# left.net
KiCad netlist of a schematic drawn in EAGLE
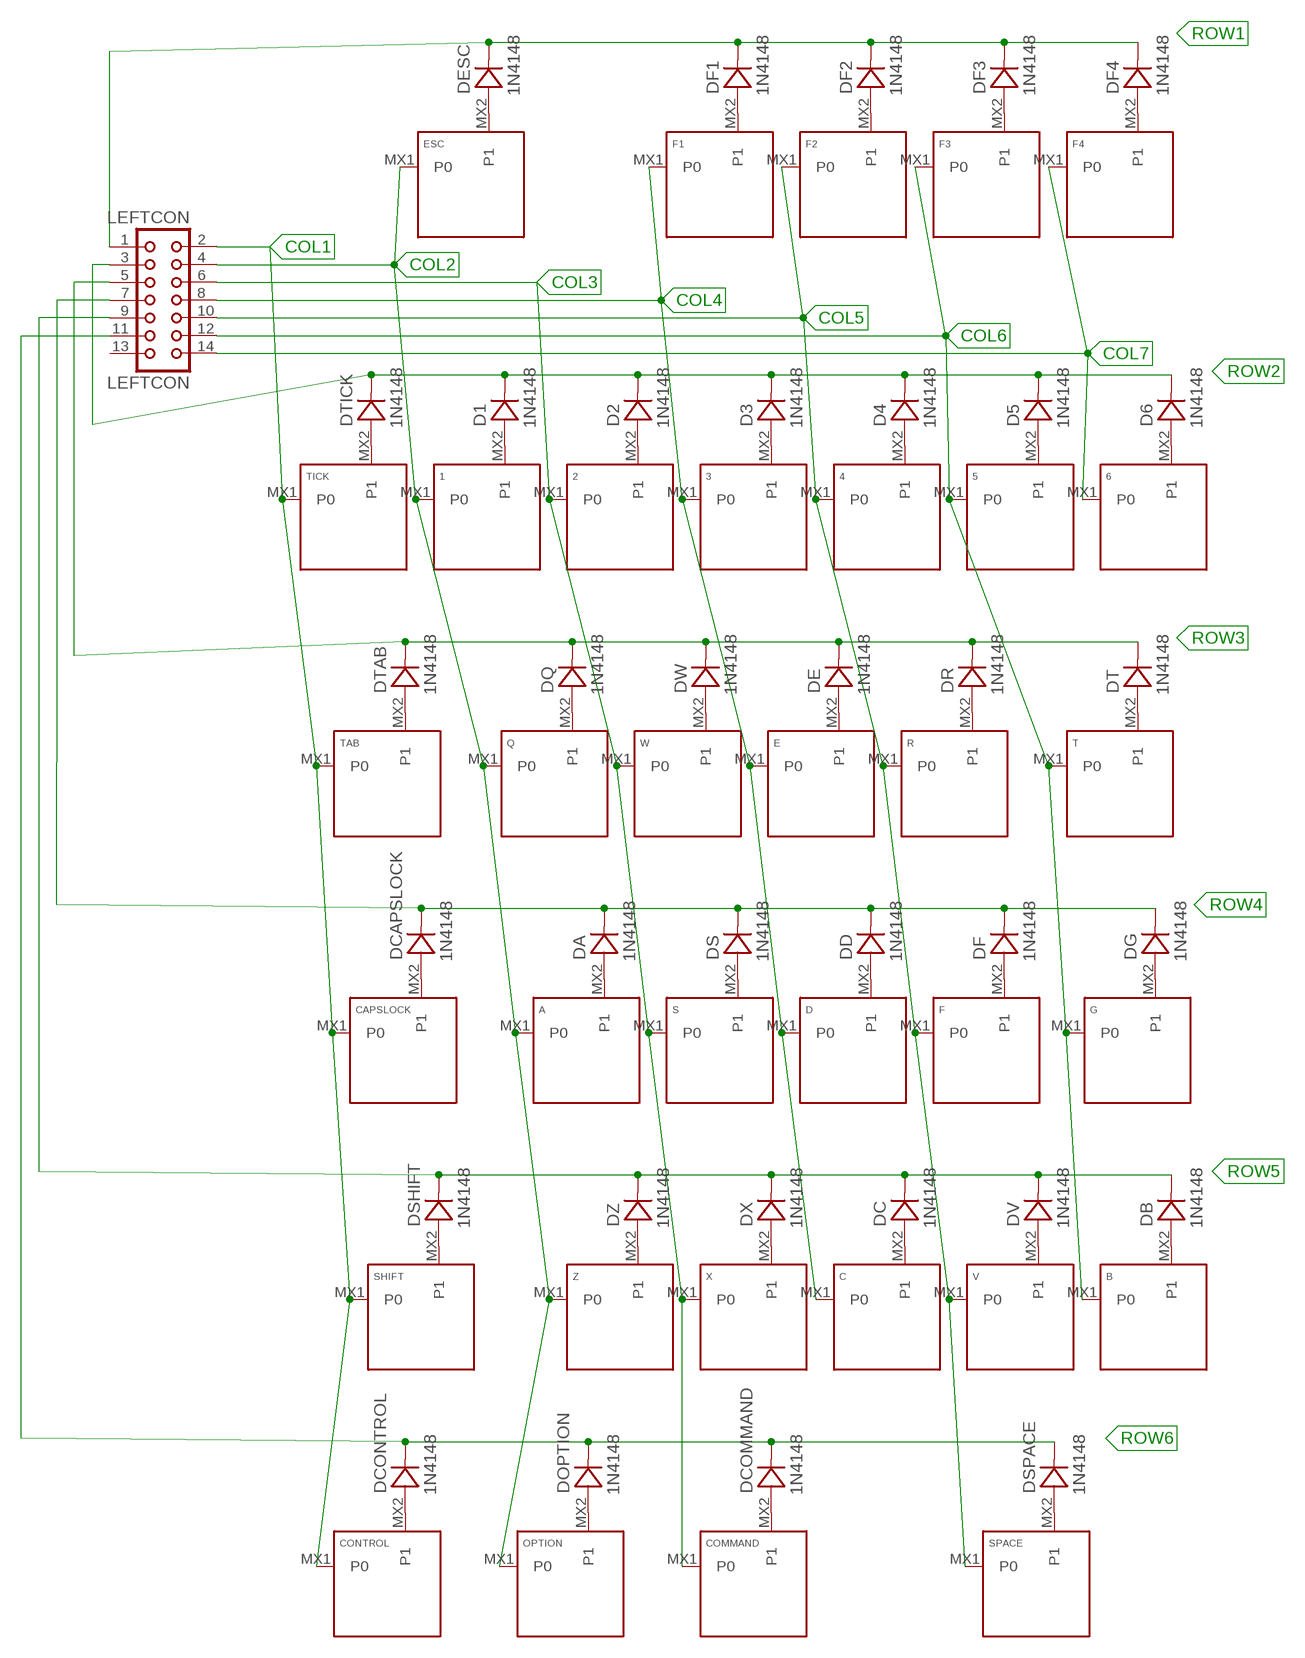
[diagram p0: schematic, sheet 1]

(export (version "E")
  (design (tool "Eeschema 10.0.6"))
  (components
    (comp (ref "1")
      (value "KEYSWITCH-PLAIN-MX-1U")
      (footprint "eagle-import:MX-1U")
      (libsource (lib "eagle-import") (part "KEYSWITCH-PLAIN-MX-1U"))
    )
    (comp (ref "2")
      (value "KEYSWITCH-PLAIN-MX-1U")
      (footprint "eagle-import:MX-1U")
      (libsource (lib "eagle-import") (part "KEYSWITCH-PLAIN-MX-1U"))
    )
    (comp (ref "3")
      (value "KEYSWITCH-PLAIN-MX-1U")
      (footprint "eagle-import:MX-1U")
      (libsource (lib "eagle-import") (part "KEYSWITCH-PLAIN-MX-1U"))
    )
    (comp (ref "4")
      (value "KEYSWITCH-PLAIN-MX-1U")
      (footprint "eagle-import:MX-1U")
      (libsource (lib "eagle-import") (part "KEYSWITCH-PLAIN-MX-1U"))
    )
    (comp (ref "5")
      (value "KEYSWITCH-PLAIN-MX-1U")
      (footprint "eagle-import:MX-1U")
      (libsource (lib "eagle-import") (part "KEYSWITCH-PLAIN-MX-1U"))
    )
    (comp (ref "6")
      (value "KEYSWITCH-PLAIN-MX-1U")
      (footprint "eagle-import:MX-1U")
      (libsource (lib "eagle-import") (part "KEYSWITCH-PLAIN-MX-1U"))
    )
    (comp (ref "A")
      (value "KEYSWITCH-PLAIN-MX-1U")
      (footprint "eagle-import:MX-1U")
      (libsource (lib "eagle-import") (part "KEYSWITCH-PLAIN-MX-1U"))
    )
    (comp (ref "B")
      (value "KEYSWITCH-PLAIN-MX-1U")
      (footprint "eagle-import:MX-1U")
      (libsource (lib "eagle-import") (part "KEYSWITCH-PLAIN-MX-1U"))
    )
    (comp (ref "C")
      (value "KEYSWITCH-PLAIN-MX-1U")
      (footprint "eagle-import:MX-1U")
      (libsource (lib "eagle-import") (part "KEYSWITCH-PLAIN-MX-1U"))
    )
    (comp (ref "CAPSLOCK")
      (value "KEYSWITCH-PLAIN-MX-1U")
      (footprint "eagle-import:MX-1U")
      (libsource (lib "eagle-import") (part "KEYSWITCH-PLAIN-MX-1U"))
    )
    (comp (ref "COMMAND")
      (value "KEYSWITCH-PLAIN-MX-1U")
      (footprint "eagle-import:MX-1U")
      (libsource (lib "eagle-import") (part "KEYSWITCH-PLAIN-MX-1U"))
    )
    (comp (ref "CONTROL")
      (value "KEYSWITCH-PLAIN-MX-1U")
      (footprint "eagle-import:MX-1U")
      (libsource (lib "eagle-import") (part "KEYSWITCH-PLAIN-MX-1U"))
    )
    (comp (ref "D")
      (value "KEYSWITCH-PLAIN-MX-1U")
      (footprint "eagle-import:MX-1U")
      (libsource (lib "eagle-import") (part "KEYSWITCH-PLAIN-MX-1U"))
    )
    (comp (ref "D1")
      (value "1N4148")
      (footprint "eagle-import:DO-35")
      (libsource (lib "eagle-import") (part "DIODE-DO-35"))
    )
    (comp (ref "D2")
      (value "1N4148")
      (footprint "eagle-import:DO-35")
      (libsource (lib "eagle-import") (part "DIODE-DO-35"))
    )
    (comp (ref "D3")
      (value "1N4148")
      (footprint "eagle-import:DO-35")
      (libsource (lib "eagle-import") (part "DIODE-DO-35"))
    )
    (comp (ref "D4")
      (value "1N4148")
      (footprint "eagle-import:DO-35")
      (libsource (lib "eagle-import") (part "DIODE-DO-35"))
    )
    (comp (ref "D5")
      (value "1N4148")
      (footprint "eagle-import:DO-35")
      (libsource (lib "eagle-import") (part "DIODE-DO-35"))
    )
    (comp (ref "D6")
      (value "1N4148")
      (footprint "eagle-import:DO-35")
      (libsource (lib "eagle-import") (part "DIODE-DO-35"))
    )
    (comp (ref "DA")
      (value "1N4148")
      (footprint "eagle-import:DO-35")
      (libsource (lib "eagle-import") (part "DIODE-DO-35"))
    )
    (comp (ref "DB")
      (value "1N4148")
      (footprint "eagle-import:DO-35")
      (libsource (lib "eagle-import") (part "DIODE-DO-35"))
    )
    (comp (ref "DC")
      (value "1N4148")
      (footprint "eagle-import:DO-35")
      (libsource (lib "eagle-import") (part "DIODE-DO-35"))
    )
    (comp (ref "DCAPSLOCK")
      (value "1N4148")
      (footprint "eagle-import:DO-35")
      (libsource (lib "eagle-import") (part "DIODE-DO-35"))
    )
    (comp (ref "DCOMMAND")
      (value "1N4148")
      (footprint "eagle-import:DO-35")
      (libsource (lib "eagle-import") (part "DIODE-DO-35"))
    )
    (comp (ref "DCONTROL")
      (value "1N4148")
      (footprint "eagle-import:DO-35")
      (libsource (lib "eagle-import") (part "DIODE-DO-35"))
    )
    (comp (ref "DD")
      (value "1N4148")
      (footprint "eagle-import:DO-35")
      (libsource (lib "eagle-import") (part "DIODE-DO-35"))
    )
    (comp (ref "DE")
      (value "1N4148")
      (footprint "eagle-import:DO-35")
      (libsource (lib "eagle-import") (part "DIODE-DO-35"))
    )
    (comp (ref "DESC")
      (value "1N4148")
      (footprint "eagle-import:DO-35")
      (libsource (lib "eagle-import") (part "DIODE-DO-35"))
    )
    (comp (ref "DF")
      (value "1N4148")
      (footprint "eagle-import:DO-35")
      (libsource (lib "eagle-import") (part "DIODE-DO-35"))
    )
    (comp (ref "DF1")
      (value "1N4148")
      (footprint "eagle-import:DO-35")
      (libsource (lib "eagle-import") (part "DIODE-DO-35"))
    )
    (comp (ref "DF2")
      (value "1N4148")
      (footprint "eagle-import:DO-35")
      (libsource (lib "eagle-import") (part "DIODE-DO-35"))
    )
    (comp (ref "DF3")
      (value "1N4148")
      (footprint "eagle-import:DO-35")
      (libsource (lib "eagle-import") (part "DIODE-DO-35"))
    )
    (comp (ref "DF4")
      (value "1N4148")
      (footprint "eagle-import:DO-35")
      (libsource (lib "eagle-import") (part "DIODE-DO-35"))
    )
    (comp (ref "DG")
      (value "1N4148")
      (footprint "eagle-import:DO-35")
      (libsource (lib "eagle-import") (part "DIODE-DO-35"))
    )
    (comp (ref "DOPTION")
      (value "1N4148")
      (footprint "eagle-import:DO-35")
      (libsource (lib "eagle-import") (part "DIODE-DO-35"))
    )
    (comp (ref "DQ")
      (value "1N4148")
      (footprint "eagle-import:DO-35")
      (libsource (lib "eagle-import") (part "DIODE-DO-35"))
    )
    (comp (ref "DR")
      (value "1N4148")
      (footprint "eagle-import:DO-35")
      (libsource (lib "eagle-import") (part "DIODE-DO-35"))
    )
    (comp (ref "DS")
      (value "1N4148")
      (footprint "eagle-import:DO-35")
      (libsource (lib "eagle-import") (part "DIODE-DO-35"))
    )
    (comp (ref "DSHIFT")
      (value "1N4148")
      (footprint "eagle-import:DO-35")
      (libsource (lib "eagle-import") (part "DIODE-DO-35"))
    )
    (comp (ref "DSPACE")
      (value "1N4148")
      (footprint "eagle-import:DO-35")
      (libsource (lib "eagle-import") (part "DIODE-DO-35"))
    )
    (comp (ref "DT")
      (value "1N4148")
      (footprint "eagle-import:DO-35")
      (libsource (lib "eagle-import") (part "DIODE-DO-35"))
    )
    (comp (ref "DTAB")
      (value "1N4148")
      (footprint "eagle-import:DO-35")
      (libsource (lib "eagle-import") (part "DIODE-DO-35"))
    )
    (comp (ref "DTICK")
      (value "1N4148")
      (footprint "eagle-import:DO-35")
      (libsource (lib "eagle-import") (part "DIODE-DO-35"))
    )
    (comp (ref "DV")
      (value "1N4148")
      (footprint "eagle-import:DO-35")
      (libsource (lib "eagle-import") (part "DIODE-DO-35"))
    )
    (comp (ref "DW")
      (value "1N4148")
      (footprint "eagle-import:DO-35")
      (libsource (lib "eagle-import") (part "DIODE-DO-35"))
    )
    (comp (ref "DX")
      (value "1N4148")
      (footprint "eagle-import:DO-35")
      (libsource (lib "eagle-import") (part "DIODE-DO-35"))
    )
    (comp (ref "DZ")
      (value "1N4148")
      (footprint "eagle-import:DO-35")
      (libsource (lib "eagle-import") (part "DIODE-DO-35"))
    )
    (comp (ref "E")
      (value "KEYSWITCH-PLAIN-MX-1U")
      (footprint "eagle-import:MX-1U")
      (libsource (lib "eagle-import") (part "KEYSWITCH-PLAIN-MX-1U"))
    )
    (comp (ref "ESC")
      (value "KEYSWITCH-PLAIN-MX-1U")
      (footprint "eagle-import:MX-1U")
      (libsource (lib "eagle-import") (part "KEYSWITCH-PLAIN-MX-1U"))
    )
    (comp (ref "F")
      (value "KEYSWITCH-PLAIN-MX-1U")
      (footprint "eagle-import:MX-1U")
      (libsource (lib "eagle-import") (part "KEYSWITCH-PLAIN-MX-1U"))
    )
    (comp (ref "F1")
      (value "KEYSWITCH-PLAIN-MX-1U")
      (footprint "eagle-import:MX-1U")
      (libsource (lib "eagle-import") (part "KEYSWITCH-PLAIN-MX-1U"))
    )
    (comp (ref "F2")
      (value "KEYSWITCH-PLAIN-MX-1U")
      (footprint "eagle-import:MX-1U")
      (libsource (lib "eagle-import") (part "KEYSWITCH-PLAIN-MX-1U"))
    )
    (comp (ref "F3")
      (value "KEYSWITCH-PLAIN-MX-1U")
      (footprint "eagle-import:MX-1U")
      (libsource (lib "eagle-import") (part "KEYSWITCH-PLAIN-MX-1U"))
    )
    (comp (ref "F4")
      (value "KEYSWITCH-PLAIN-MX-1U")
      (footprint "eagle-import:MX-1U")
      (libsource (lib "eagle-import") (part "KEYSWITCH-PLAIN-MX-1U"))
    )
    (comp (ref "G")
      (value "KEYSWITCH-PLAIN-MX-1U")
      (footprint "eagle-import:MX-1U")
      (libsource (lib "eagle-import") (part "KEYSWITCH-PLAIN-MX-1U"))
    )
    (comp (ref "LEFTCON")
      (value "LEFTCON")
      (footprint "eagle-import:CON14")
      (libsource (lib "eagle-import") (part "CON14"))
    )
    (comp (ref "OPTION")
      (value "KEYSWITCH-PLAIN-MX-1U")
      (footprint "eagle-import:MX-1U")
      (libsource (lib "eagle-import") (part "KEYSWITCH-PLAIN-MX-1U"))
    )
    (comp (ref "Q")
      (value "KEYSWITCH-PLAIN-MX-1U")
      (footprint "eagle-import:MX-1U")
      (libsource (lib "eagle-import") (part "KEYSWITCH-PLAIN-MX-1U"))
    )
    (comp (ref "R")
      (value "KEYSWITCH-PLAIN-MX-1U")
      (footprint "eagle-import:MX-1U")
      (libsource (lib "eagle-import") (part "KEYSWITCH-PLAIN-MX-1U"))
    )
    (comp (ref "S")
      (value "KEYSWITCH-PLAIN-MX-1U")
      (footprint "eagle-import:MX-1U")
      (libsource (lib "eagle-import") (part "KEYSWITCH-PLAIN-MX-1U"))
    )
    (comp (ref "SHIFT")
      (value "KEYSWITCH-PLAIN-MX-2U")
      (footprint "eagle-import:MX-2U")
      (libsource (lib "eagle-import") (part "KEYSWITCH-PLAIN-MX-2U"))
    )
    (comp (ref "SPACE")
      (value "KEYSWITCH-PLAIN-MX-2U")
      (footprint "eagle-import:MX-2U")
      (libsource (lib "eagle-import") (part "KEYSWITCH-PLAIN-MX-2U"))
    )
    (comp (ref "T")
      (value "KEYSWITCH-PLAIN-MX-1U")
      (footprint "eagle-import:MX-1U")
      (libsource (lib "eagle-import") (part "KEYSWITCH-PLAIN-MX-1U"))
    )
    (comp (ref "TAB")
      (value "KEYSWITCH-PLAIN-MX-1U")
      (footprint "eagle-import:MX-1U")
      (libsource (lib "eagle-import") (part "KEYSWITCH-PLAIN-MX-1U"))
    )
    (comp (ref "TICK")
      (value "KEYSWITCH-PLAIN-MX-1U")
      (footprint "eagle-import:MX-1U")
      (libsource (lib "eagle-import") (part "KEYSWITCH-PLAIN-MX-1U"))
    )
    (comp (ref "V")
      (value "KEYSWITCH-PLAIN-MX-1U")
      (footprint "eagle-import:MX-1U")
      (libsource (lib "eagle-import") (part "KEYSWITCH-PLAIN-MX-1U"))
    )
    (comp (ref "W")
      (value "KEYSWITCH-PLAIN-MX-1U")
      (footprint "eagle-import:MX-1U")
      (libsource (lib "eagle-import") (part "KEYSWITCH-PLAIN-MX-1U"))
    )
    (comp (ref "X")
      (value "KEYSWITCH-PLAIN-MX-1U")
      (footprint "eagle-import:MX-1U")
      (libsource (lib "eagle-import") (part "KEYSWITCH-PLAIN-MX-1U"))
    )
    (comp (ref "Z")
      (value "KEYSWITCH-PLAIN-MX-1U")
      (footprint "eagle-import:MX-1U")
      (libsource (lib "eagle-import") (part "KEYSWITCH-PLAIN-MX-1U"))
    )
  )
  (nets
    (net (code "1") (name "COL1") (class "Default")
      (node (ref "CAPSLOCK") (pin "MX1") (pinfunction "P0_MX1") (pintype "bidirectional"))
      (node (ref "CONTROL") (pin "MX1") (pinfunction "P0_MX1") (pintype "bidirectional"))
      (node (ref "LEFTCON") (pin "2") (pinfunction "2_2") (pintype "passive"))
      (node (ref "SHIFT") (pin "MX1") (pinfunction "P0_MX1") (pintype "bidirectional"))
      (node (ref "TAB") (pin "MX1") (pinfunction "P0_MX1") (pintype "bidirectional"))
      (node (ref "TICK") (pin "MX1") (pinfunction "P0_MX1") (pintype "bidirectional"))
    )
    (net (code "2") (name "COL2") (class "Default")
      (node (ref "1") (pin "MX1") (pinfunction "P0_MX1") (pintype "bidirectional"))
      (node (ref "A") (pin "MX1") (pinfunction "P0_MX1") (pintype "bidirectional"))
      (node (ref "ESC") (pin "MX1") (pinfunction "P0_MX1") (pintype "bidirectional"))
      (node (ref "LEFTCON") (pin "4") (pinfunction "4_4") (pintype "passive"))
      (node (ref "OPTION") (pin "MX1") (pinfunction "P0_MX1") (pintype "bidirectional"))
      (node (ref "Q") (pin "MX1") (pinfunction "P0_MX1") (pintype "bidirectional"))
      (node (ref "Z") (pin "MX1") (pinfunction "P0_MX1") (pintype "bidirectional"))
    )
    (net (code "3") (name "COL3") (class "Default")
      (node (ref "2") (pin "MX1") (pinfunction "P0_MX1") (pintype "bidirectional"))
      (node (ref "COMMAND") (pin "MX1") (pinfunction "P0_MX1") (pintype "bidirectional"))
      (node (ref "LEFTCON") (pin "6") (pinfunction "6_6") (pintype "passive"))
      (node (ref "S") (pin "MX1") (pinfunction "P0_MX1") (pintype "bidirectional"))
      (node (ref "W") (pin "MX1") (pinfunction "P0_MX1") (pintype "bidirectional"))
      (node (ref "X") (pin "MX1") (pinfunction "P0_MX1") (pintype "bidirectional"))
    )
    (net (code "4") (name "COL4") (class "Default")
      (node (ref "3") (pin "MX1") (pinfunction "P0_MX1") (pintype "bidirectional"))
      (node (ref "C") (pin "MX1") (pinfunction "P0_MX1") (pintype "bidirectional"))
      (node (ref "D") (pin "MX1") (pinfunction "P0_MX1") (pintype "bidirectional"))
      (node (ref "E") (pin "MX1") (pinfunction "P0_MX1") (pintype "bidirectional"))
      (node (ref "F1") (pin "MX1") (pinfunction "P0_MX1") (pintype "bidirectional"))
      (node (ref "LEFTCON") (pin "8") (pinfunction "8_8") (pintype "passive"))
    )
    (net (code "5") (name "COL5") (class "Default")
      (node (ref "4") (pin "MX1") (pinfunction "P0_MX1") (pintype "bidirectional"))
      (node (ref "F") (pin "MX1") (pinfunction "P0_MX1") (pintype "bidirectional"))
      (node (ref "F2") (pin "MX1") (pinfunction "P0_MX1") (pintype "bidirectional"))
      (node (ref "LEFTCON") (pin "10") (pinfunction "10_10") (pintype "passive"))
      (node (ref "R") (pin "MX1") (pinfunction "P0_MX1") (pintype "bidirectional"))
      (node (ref "SPACE") (pin "MX1") (pinfunction "P0_MX1") (pintype "bidirectional"))
      (node (ref "V") (pin "MX1") (pinfunction "P0_MX1") (pintype "bidirectional"))
    )
    (net (code "6") (name "COL6") (class "Default")
      (node (ref "5") (pin "MX1") (pinfunction "P0_MX1") (pintype "bidirectional"))
      (node (ref "B") (pin "MX1") (pinfunction "P0_MX1") (pintype "bidirectional"))
      (node (ref "F3") (pin "MX1") (pinfunction "P0_MX1") (pintype "bidirectional"))
      (node (ref "G") (pin "MX1") (pinfunction "P0_MX1") (pintype "bidirectional"))
      (node (ref "LEFTCON") (pin "12") (pinfunction "12_12") (pintype "passive"))
      (node (ref "T") (pin "MX1") (pinfunction "P0_MX1") (pintype "bidirectional"))
    )
    (net (code "7") (name "COL7") (class "Default")
      (node (ref "6") (pin "MX1") (pinfunction "P0_MX1") (pintype "bidirectional"))
      (node (ref "F4") (pin "MX1") (pinfunction "P0_MX1") (pintype "bidirectional"))
      (node (ref "LEFTCON") (pin "14") (pinfunction "14_14") (pintype "passive"))
    )
    (net (code "8") (name "Net-(1-P1)") (class "Default")
      (node (ref "1") (pin "MX2") (pinfunction "P1_MX2") (pintype "bidirectional"))
      (node (ref "D1") (pin "A") (pinfunction "A_A") (pintype "passive"))
    )
    (net (code "9") (name "Net-(2-P1)") (class "Default")
      (node (ref "2") (pin "MX2") (pinfunction "P1_MX2") (pintype "bidirectional"))
      (node (ref "D2") (pin "A") (pinfunction "A_A") (pintype "passive"))
    )
    (net (code "10") (name "Net-(3-P1)") (class "Default")
      (node (ref "3") (pin "MX2") (pinfunction "P1_MX2") (pintype "bidirectional"))
      (node (ref "D3") (pin "A") (pinfunction "A_A") (pintype "passive"))
    )
    (net (code "11") (name "Net-(4-P1)") (class "Default")
      (node (ref "4") (pin "MX2") (pinfunction "P1_MX2") (pintype "bidirectional"))
      (node (ref "D4") (pin "A") (pinfunction "A_A") (pintype "passive"))
    )
    (net (code "12") (name "Net-(5-P1)") (class "Default")
      (node (ref "5") (pin "MX2") (pinfunction "P1_MX2") (pintype "bidirectional"))
      (node (ref "D5") (pin "A") (pinfunction "A_A") (pintype "passive"))
    )
    (net (code "13") (name "Net-(6-P1)") (class "Default")
      (node (ref "6") (pin "MX2") (pinfunction "P1_MX2") (pintype "bidirectional"))
      (node (ref "D6") (pin "A") (pinfunction "A_A") (pintype "passive"))
    )
    (net (code "14") (name "Net-(A-P1)") (class "Default")
      (node (ref "A") (pin "MX2") (pinfunction "P1_MX2") (pintype "bidirectional"))
      (node (ref "DA") (pin "A") (pinfunction "A_A") (pintype "passive"))
    )
    (net (code "15") (name "Net-(B-P1)") (class "Default")
      (node (ref "B") (pin "MX2") (pinfunction "P1_MX2") (pintype "bidirectional"))
      (node (ref "DB") (pin "A") (pinfunction "A_A") (pintype "passive"))
    )
    (net (code "16") (name "Net-(C-P1)") (class "Default")
      (node (ref "C") (pin "MX2") (pinfunction "P1_MX2") (pintype "bidirectional"))
      (node (ref "DC") (pin "A") (pinfunction "A_A") (pintype "passive"))
    )
    (net (code "17") (name "Net-(CAPSLOCK-P1)") (class "Default")
      (node (ref "CAPSLOCK") (pin "MX2") (pinfunction "P1_MX2") (pintype "bidirectional"))
      (node (ref "DCAPSLOCK") (pin "A") (pinfunction "A_A") (pintype "passive"))
    )
    (net (code "18") (name "Net-(COMMAND-P1)") (class "Default")
      (node (ref "COMMAND") (pin "MX2") (pinfunction "P1_MX2") (pintype "bidirectional"))
      (node (ref "DCOMMAND") (pin "A") (pinfunction "A_A") (pintype "passive"))
    )
    (net (code "19") (name "Net-(CONTROL-P1)") (class "Default")
      (node (ref "CONTROL") (pin "MX2") (pinfunction "P1_MX2") (pintype "bidirectional"))
      (node (ref "DCONTROL") (pin "A") (pinfunction "A_A") (pintype "passive"))
    )
    (net (code "20") (name "Net-(D-P1)") (class "Default")
      (node (ref "D") (pin "MX2") (pinfunction "P1_MX2") (pintype "bidirectional"))
      (node (ref "DD") (pin "A") (pinfunction "A_A") (pintype "passive"))
    )
    (net (code "21") (name "Net-(E-P1)") (class "Default")
      (node (ref "DE") (pin "A") (pinfunction "A_A") (pintype "passive"))
      (node (ref "E") (pin "MX2") (pinfunction "P1_MX2") (pintype "bidirectional"))
    )
    (net (code "22") (name "Net-(ESC-P1)") (class "Default")
      (node (ref "DESC") (pin "A") (pinfunction "A_A") (pintype "passive"))
      (node (ref "ESC") (pin "MX2") (pinfunction "P1_MX2") (pintype "bidirectional"))
    )
    (net (code "23") (name "Net-(F-P1)") (class "Default")
      (node (ref "DF") (pin "A") (pinfunction "A_A") (pintype "passive"))
      (node (ref "F") (pin "MX2") (pinfunction "P1_MX2") (pintype "bidirectional"))
    )
    (net (code "24") (name "Net-(F1-P1)") (class "Default")
      (node (ref "DF1") (pin "A") (pinfunction "A_A") (pintype "passive"))
      (node (ref "F1") (pin "MX2") (pinfunction "P1_MX2") (pintype "bidirectional"))
    )
    (net (code "25") (name "Net-(F2-P1)") (class "Default")
      (node (ref "DF2") (pin "A") (pinfunction "A_A") (pintype "passive"))
      (node (ref "F2") (pin "MX2") (pinfunction "P1_MX2") (pintype "bidirectional"))
    )
    (net (code "26") (name "Net-(F3-P1)") (class "Default")
      (node (ref "DF3") (pin "A") (pinfunction "A_A") (pintype "passive"))
      (node (ref "F3") (pin "MX2") (pinfunction "P1_MX2") (pintype "bidirectional"))
    )
    (net (code "27") (name "Net-(F4-P1)") (class "Default")
      (node (ref "DF4") (pin "A") (pinfunction "A_A") (pintype "passive"))
      (node (ref "F4") (pin "MX2") (pinfunction "P1_MX2") (pintype "bidirectional"))
    )
    (net (code "28") (name "Net-(G-P1)") (class "Default")
      (node (ref "DG") (pin "A") (pinfunction "A_A") (pintype "passive"))
      (node (ref "G") (pin "MX2") (pinfunction "P1_MX2") (pintype "bidirectional"))
    )
    (net (code "29") (name "Net-(OPTION-P1)") (class "Default")
      (node (ref "DOPTION") (pin "A") (pinfunction "A_A") (pintype "passive"))
      (node (ref "OPTION") (pin "MX2") (pinfunction "P1_MX2") (pintype "bidirectional"))
    )
    (net (code "30") (name "Net-(Q-P1)") (class "Default")
      (node (ref "DQ") (pin "A") (pinfunction "A_A") (pintype "passive"))
      (node (ref "Q") (pin "MX2") (pinfunction "P1_MX2") (pintype "bidirectional"))
    )
    (net (code "31") (name "Net-(R-P1)") (class "Default")
      (node (ref "DR") (pin "A") (pinfunction "A_A") (pintype "passive"))
      (node (ref "R") (pin "MX2") (pinfunction "P1_MX2") (pintype "bidirectional"))
    )
    (net (code "32") (name "Net-(S-P1)") (class "Default")
      (node (ref "DS") (pin "A") (pinfunction "A_A") (pintype "passive"))
      (node (ref "S") (pin "MX2") (pinfunction "P1_MX2") (pintype "bidirectional"))
    )
    (net (code "33") (name "Net-(SHIFT-P1)") (class "Default")
      (node (ref "DSHIFT") (pin "A") (pinfunction "A_A") (pintype "passive"))
      (node (ref "SHIFT") (pin "MX2") (pinfunction "P1_MX2") (pintype "bidirectional"))
    )
    (net (code "34") (name "Net-(SPACE-P1)") (class "Default")
      (node (ref "DSPACE") (pin "A") (pinfunction "A_A") (pintype "passive"))
      (node (ref "SPACE") (pin "MX2") (pinfunction "P1_MX2") (pintype "bidirectional"))
    )
    (net (code "35") (name "Net-(T-P1)") (class "Default")
      (node (ref "DT") (pin "A") (pinfunction "A_A") (pintype "passive"))
      (node (ref "T") (pin "MX2") (pinfunction "P1_MX2") (pintype "bidirectional"))
    )
    (net (code "36") (name "Net-(TAB-P1)") (class "Default")
      (node (ref "DTAB") (pin "A") (pinfunction "A_A") (pintype "passive"))
      (node (ref "TAB") (pin "MX2") (pinfunction "P1_MX2") (pintype "bidirectional"))
    )
    (net (code "37") (name "Net-(TICK-P1)") (class "Default")
      (node (ref "DTICK") (pin "A") (pinfunction "A_A") (pintype "passive"))
      (node (ref "TICK") (pin "MX2") (pinfunction "P1_MX2") (pintype "bidirectional"))
    )
    (net (code "38") (name "Net-(V-P1)") (class "Default")
      (node (ref "DV") (pin "A") (pinfunction "A_A") (pintype "passive"))
      (node (ref "V") (pin "MX2") (pinfunction "P1_MX2") (pintype "bidirectional"))
    )
    (net (code "39") (name "Net-(W-P1)") (class "Default")
      (node (ref "DW") (pin "A") (pinfunction "A_A") (pintype "passive"))
      (node (ref "W") (pin "MX2") (pinfunction "P1_MX2") (pintype "bidirectional"))
    )
    (net (code "40") (name "Net-(X-P1)") (class "Default")
      (node (ref "DX") (pin "A") (pinfunction "A_A") (pintype "passive"))
      (node (ref "X") (pin "MX2") (pinfunction "P1_MX2") (pintype "bidirectional"))
    )
    (net (code "41") (name "Net-(Z-P1)") (class "Default")
      (node (ref "DZ") (pin "A") (pinfunction "A_A") (pintype "passive"))
      (node (ref "Z") (pin "MX2") (pinfunction "P1_MX2") (pintype "bidirectional"))
    )
    (net (code "42") (name "ROW1") (class "Default")
      (node (ref "DESC") (pin "C") (pinfunction "C_C") (pintype "passive"))
      (node (ref "DF1") (pin "C") (pinfunction "C_C") (pintype "passive"))
      (node (ref "DF2") (pin "C") (pinfunction "C_C") (pintype "passive"))
      (node (ref "DF3") (pin "C") (pinfunction "C_C") (pintype "passive"))
      (node (ref "DF4") (pin "C") (pinfunction "C_C") (pintype "passive"))
      (node (ref "LEFTCON") (pin "1") (pinfunction "1_1") (pintype "passive"))
    )
    (net (code "43") (name "ROW2") (class "Default")
      (node (ref "D1") (pin "C") (pinfunction "C_C") (pintype "passive"))
      (node (ref "D2") (pin "C") (pinfunction "C_C") (pintype "passive"))
      (node (ref "D3") (pin "C") (pinfunction "C_C") (pintype "passive"))
      (node (ref "D4") (pin "C") (pinfunction "C_C") (pintype "passive"))
      (node (ref "D5") (pin "C") (pinfunction "C_C") (pintype "passive"))
      (node (ref "D6") (pin "C") (pinfunction "C_C") (pintype "passive"))
      (node (ref "DTICK") (pin "C") (pinfunction "C_C") (pintype "passive"))
      (node (ref "LEFTCON") (pin "3") (pinfunction "3_3") (pintype "passive"))
    )
    (net (code "44") (name "ROW3") (class "Default")
      (node (ref "DE") (pin "C") (pinfunction "C_C") (pintype "passive"))
      (node (ref "DQ") (pin "C") (pinfunction "C_C") (pintype "passive"))
      (node (ref "DR") (pin "C") (pinfunction "C_C") (pintype "passive"))
      (node (ref "DT") (pin "C") (pinfunction "C_C") (pintype "passive"))
      (node (ref "DTAB") (pin "C") (pinfunction "C_C") (pintype "passive"))
      (node (ref "DW") (pin "C") (pinfunction "C_C") (pintype "passive"))
      (node (ref "LEFTCON") (pin "5") (pinfunction "5_5") (pintype "passive"))
    )
    (net (code "45") (name "ROW4") (class "Default")
      (node (ref "DA") (pin "C") (pinfunction "C_C") (pintype "passive"))
      (node (ref "DCAPSLOCK") (pin "C") (pinfunction "C_C") (pintype "passive"))
      (node (ref "DD") (pin "C") (pinfunction "C_C") (pintype "passive"))
      (node (ref "DF") (pin "C") (pinfunction "C_C") (pintype "passive"))
      (node (ref "DG") (pin "C") (pinfunction "C_C") (pintype "passive"))
      (node (ref "DS") (pin "C") (pinfunction "C_C") (pintype "passive"))
      (node (ref "LEFTCON") (pin "7") (pinfunction "7_7") (pintype "passive"))
    )
    (net (code "46") (name "ROW5") (class "Default")
      (node (ref "DB") (pin "C") (pinfunction "C_C") (pintype "passive"))
      (node (ref "DC") (pin "C") (pinfunction "C_C") (pintype "passive"))
      (node (ref "DSHIFT") (pin "C") (pinfunction "C_C") (pintype "passive"))
      (node (ref "DV") (pin "C") (pinfunction "C_C") (pintype "passive"))
      (node (ref "DX") (pin "C") (pinfunction "C_C") (pintype "passive"))
      (node (ref "DZ") (pin "C") (pinfunction "C_C") (pintype "passive"))
      (node (ref "LEFTCON") (pin "9") (pinfunction "9_9") (pintype "passive"))
    )
    (net (code "47") (name "ROW6") (class "Default")
      (node (ref "DCOMMAND") (pin "C") (pinfunction "C_C") (pintype "passive"))
      (node (ref "DCONTROL") (pin "C") (pinfunction "C_C") (pintype "passive"))
      (node (ref "DOPTION") (pin "C") (pinfunction "C_C") (pintype "passive"))
      (node (ref "DSPACE") (pin "C") (pinfunction "C_C") (pintype "passive"))
      (node (ref "LEFTCON") (pin "11") (pinfunction "11_11") (pintype "passive"))
    )
    (net (code "48") (name "unconnected-(LEFTCON-Pad13)") (class "Default")
      (node (ref "LEFTCON") (pin "13") (pinfunction "13_13") (pintype "passive"))
    )
  )
)
